# LoRasPI.net
KiCad netlist of a schematic drawn in EAGLE
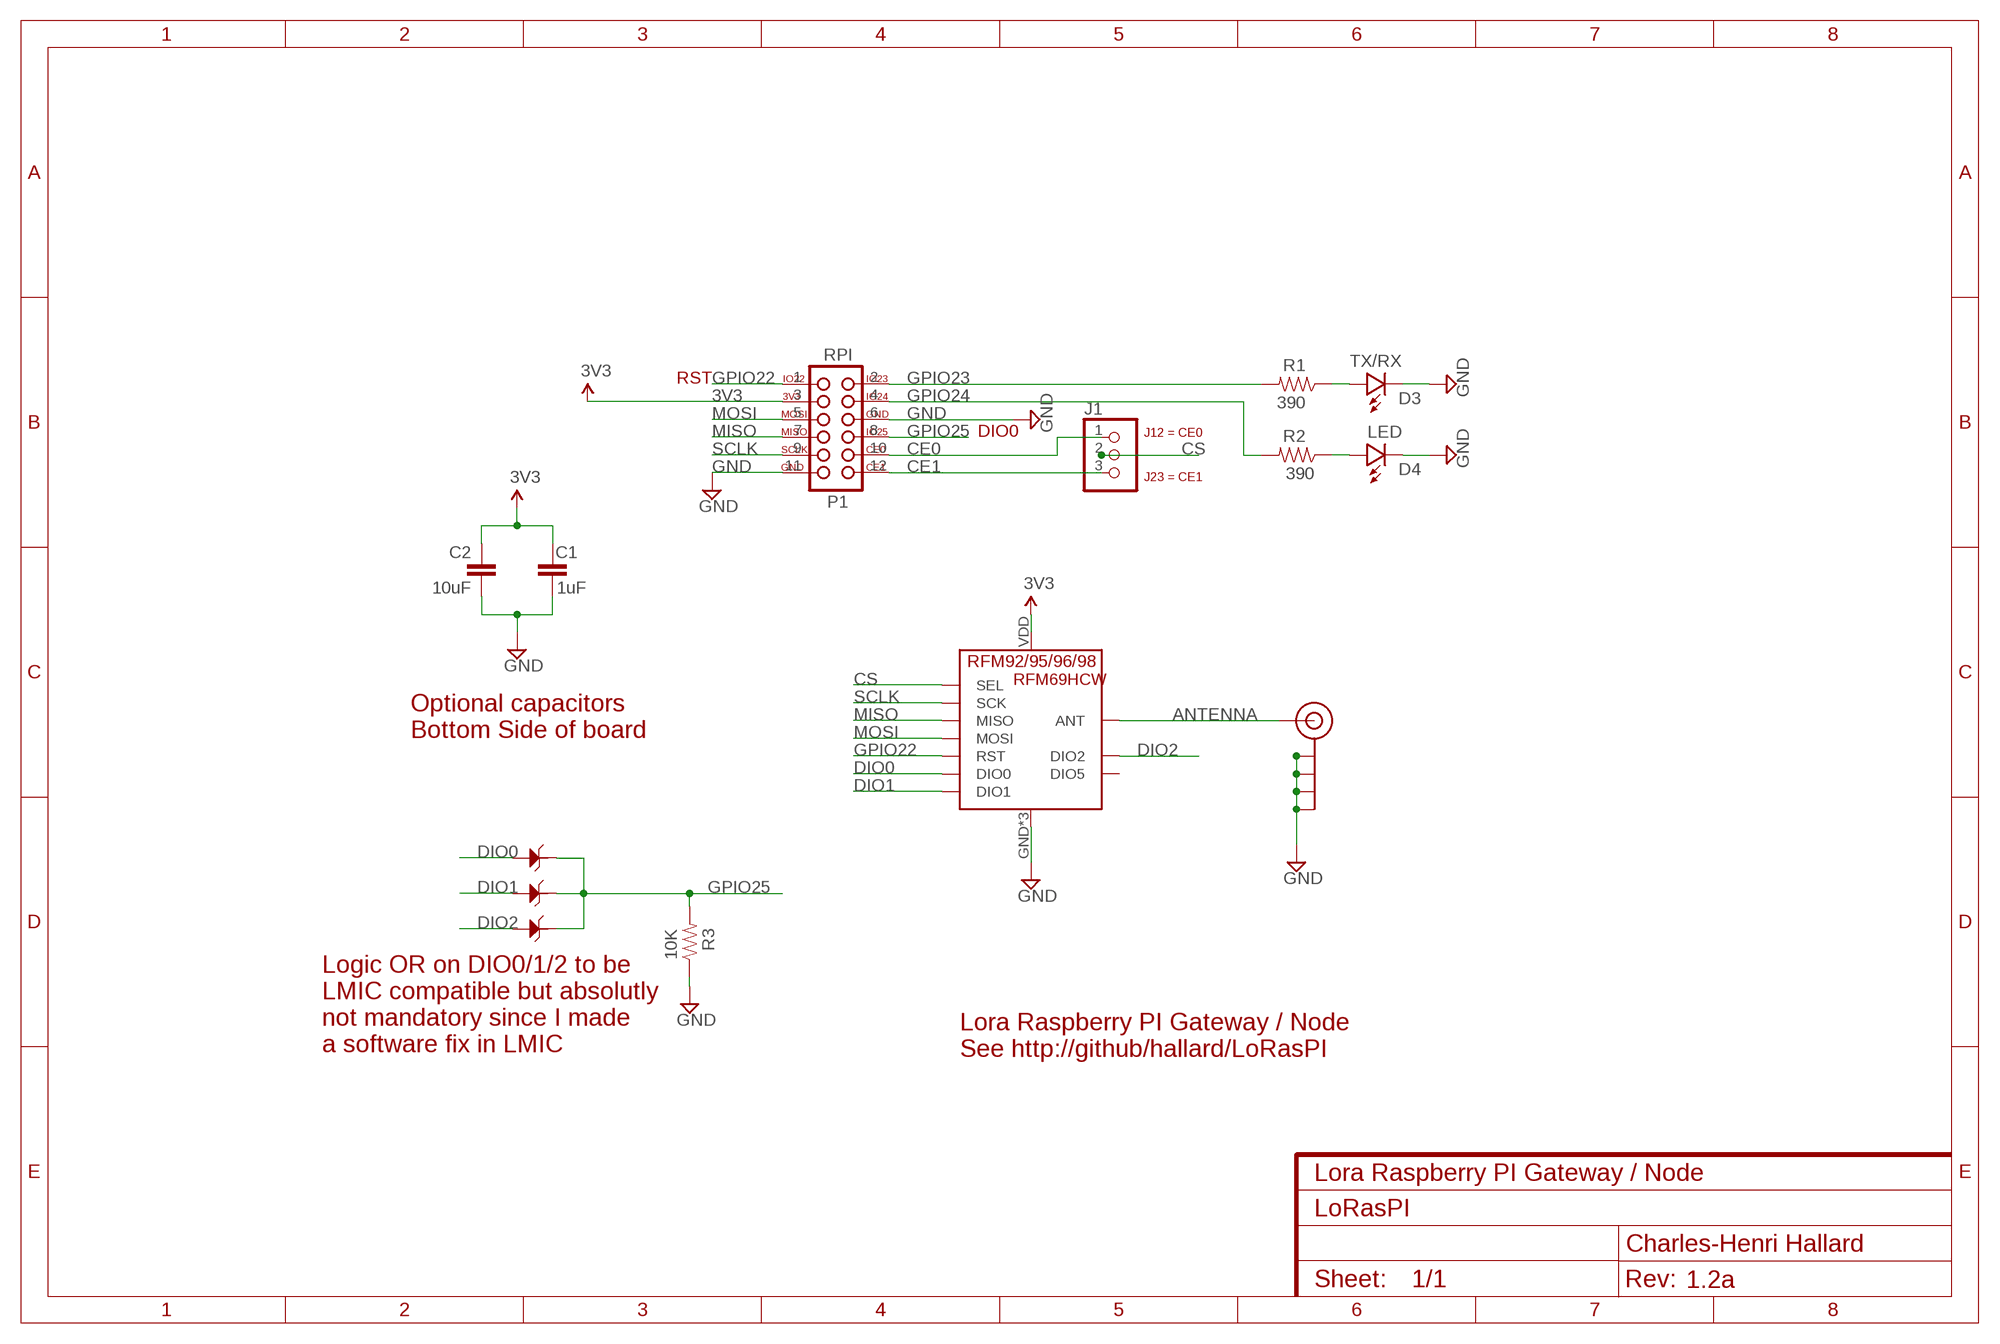
[diagram p0: schematic, sheet 1]

(export (version "E")
  (design (tool "Eeschema 10.0.6"))
  (components
    (comp (ref "C1")
      (value "1uF")
      (footprint "eagle-import:0805-CAP-LARGEPADS")
      (libsource (lib "eagle-import") (part "CAP0805-CAP-LARGEPADS"))
    )
    (comp (ref "C2")
      (value "10uF")
      (footprint "eagle-import:0805-CAP-LARGEPADS")
      (libsource (lib "eagle-import") (part "CAP0805-CAP-LARGEPADS"))
    )
    (comp (ref "D0")
      (value "1N4148")
      (footprint "eagle-import:SOD123-2.7X1.6")
      (libsource (lib "eagle-import") (part "D-ESD-2P-CESD5V0D1"))
    )
    (comp (ref "D1")
      (value "1N4148")
      (footprint "eagle-import:SOD123-2.7X1.6")
      (libsource (lib "eagle-import") (part "D-ESD-2P-CESD5V0D1"))
    )
    (comp (ref "D2")
      (value "1N4148")
      (footprint "eagle-import:SOD123-2.7X1.6")
      (libsource (lib "eagle-import") (part "D-ESD-2P-CESD5V0D1"))
    )
    (comp (ref "D3")
      (value "TX/RX")
      (footprint "eagle-import:0805-LED-LARGEPADS")
      (libsource (lib "eagle-import") (part "LED0805-LARGE"))
    )
    (comp (ref "D4")
      (value "LED")
      (footprint "eagle-import:0805-LED-LARGEPADS")
      (libsource (lib "eagle-import") (part "LED0805-LARGE"))
    )
    (comp (ref "HOPE-RF")
      (value "RFM92/95/96/98")
      (footprint "eagle-import:RFM95")
      (libsource (lib "eagle-import") (part "RFM95"))
    )
    (comp (ref "J$1")
      (value "ANTENNATINY")
      (footprint "eagle-import:SMA_UFL_PAD_TINY")
      (libsource (lib "eagle-import") (part "ANTENNATINY"))
    )
    (comp (ref "J1")
      (value "JUMPER_1X30805")
      (footprint "eagle-import:JP3_0805")
      (fields
        (field (name "J12") "optA")
        (field (name "J23") "optB")
        (field (name "J12_1") "CE0")
        (field (name "J23_1") "CE1")
      )
      (libsource (lib "eagle-import") (part "JUMPER_1X30805"))
    )
    (comp (ref "R1")
      (value "390")
      (footprint "eagle-import:0805-RES")
      (libsource (lib "eagle-import") (part "RESISTOR0805-RES"))
    )
    (comp (ref "R2")
      (value "390")
      (footprint "eagle-import:0805-RES")
      (libsource (lib "eagle-import") (part "RESISTOR0805-RES"))
    )
    (comp (ref "R3")
      (value "10K")
      (footprint "eagle-import:0805-RES")
      (libsource (lib "eagle-import") (part "RESISTOR0805-RES"))
    )
    (comp (ref "U$2")
      (value "RASPBERRY_PI_2X6_BOTTOM")
      (footprint "eagle-import:2X06_LOCK")
      (libsource (lib "eagle-import") (part "RASPBERRY_PI_2X6_BOTTOM"))
    )
  )
  (nets
    (net (code "1") (name "/ANTENNA") (class "Default")
      (node (ref "HOPE-RF") (pin "ANT") (pinfunction "ANT_ANT") (pintype "passive"))
      (node (ref "J$1") (pin "ANT1") (pinfunction "SIGNAL_ANT1") (pintype "bidirectional"))
      (node (ref "J$1") (pin "ANT2") (pinfunction "SIGNAL_ANT2") (pintype "bidirectional"))
      (node (ref "J$1") (pin "ANT3") (pinfunction "SIGNAL_ANT3") (pintype "bidirectional"))
    )
    (net (code "2") (name "/CE0") (class "Default")
      (node (ref "J1") (pin "1") (pinfunction "1_1") (pintype "passive"))
      (node (ref "U$2") (pin "10") (pinfunction "24_10") (pintype "bidirectional"))
    )
    (net (code "3") (name "/CE1") (class "Default")
      (node (ref "J1") (pin "3") (pinfunction "3_3") (pintype "passive"))
      (node (ref "U$2") (pin "12") (pinfunction "26_12") (pintype "bidirectional"))
    )
    (net (code "4") (name "/CS") (class "Default")
      (node (ref "HOPE-RF") (pin "NSS") (pinfunction "SEL_NSS") (pintype "input"))
      (node (ref "J1") (pin "2") (pinfunction "2_2") (pintype "passive"))
    )
    (net (code "5") (name "/DIO0") (class "Default")
      (node (ref "D0") (pin "1") (pinfunction "1_1") (pintype "bidirectional"))
      (node (ref "HOPE-RF") (pin "DIO0") (pinfunction "DIO0_DIO0") (pintype "open_collector"))
    )
    (net (code "6") (name "/DIO1") (class "Default")
      (node (ref "D1") (pin "1") (pinfunction "1_1") (pintype "bidirectional"))
      (node (ref "HOPE-RF") (pin "DIO1") (pinfunction "DIO1_DIO1") (pintype "open_collector"))
    )
    (net (code "7") (name "/DIO2") (class "Default")
      (node (ref "D2") (pin "1") (pinfunction "1_1") (pintype "bidirectional"))
      (node (ref "HOPE-RF") (pin "DIO2") (pinfunction "DIO2_DIO2") (pintype "open_collector"))
    )
    (net (code "8") (name "/GPIO22") (class "Default")
      (node (ref "HOPE-RF") (pin "RST") (pinfunction "RST_RST") (pintype "open_collector"))
      (node (ref "U$2") (pin "1") (pinfunction "15_1") (pintype "bidirectional"))
    )
    (net (code "9") (name "/GPIO23") (class "Default")
      (node (ref "R1") (pin "2") (pinfunction "2_2") (pintype "passive"))
      (node (ref "U$2") (pin "2") (pinfunction "16_2") (pintype "bidirectional"))
    )
    (net (code "10") (name "/GPIO24") (class "Default")
      (node (ref "R2") (pin "2") (pinfunction "2_2") (pintype "passive"))
      (node (ref "U$2") (pin "4") (pinfunction "18_4") (pintype "bidirectional"))
    )
    (net (code "11") (name "/GPIO25") (class "Default")
      (node (ref "D0") (pin "2") (pinfunction "2_2") (pintype "bidirectional"))
      (node (ref "D1") (pin "2") (pinfunction "2_2") (pintype "bidirectional"))
      (node (ref "D2") (pin "2") (pinfunction "2_2") (pintype "bidirectional"))
      (node (ref "R3") (pin "2") (pinfunction "2_2") (pintype "passive"))
      (node (ref "U$2") (pin "8") (pinfunction "22_8") (pintype "bidirectional"))
    )
    (net (code "12") (name "/MISO") (class "Default")
      (node (ref "HOPE-RF") (pin "MISO") (pinfunction "MISO_MISO") (pintype "input"))
      (node (ref "U$2") (pin "7") (pinfunction "21_7") (pintype "bidirectional"))
    )
    (net (code "13") (name "/MOSI") (class "Default")
      (node (ref "HOPE-RF") (pin "MOSI") (pinfunction "MOSI_MOSI") (pintype "output"))
      (node (ref "U$2") (pin "5") (pinfunction "19_5") (pintype "bidirectional"))
    )
    (net (code "14") (name "/SCLK") (class "Default")
      (node (ref "HOPE-RF") (pin "SCK") (pinfunction "SCK_SCK") (pintype "input"))
      (node (ref "U$2") (pin "9") (pinfunction "23_9") (pintype "bidirectional"))
    )
    (net (code "15") (name "3V3") (class "Default")
      (node (ref "C1") (pin "2") (pinfunction "2_2") (pintype "passive"))
      (node (ref "C2") (pin "2") (pinfunction "2_2") (pintype "passive"))
      (node (ref "HOPE-RF") (pin "VDD") (pinfunction "VCC_VDD") (pintype "power_in"))
      (node (ref "U$2") (pin "3") (pinfunction "17_3") (pintype "power_in"))
    )
    (net (code "16") (name "GND") (class "Default")
      (node (ref "C1") (pin "1") (pinfunction "1_1") (pintype "passive"))
      (node (ref "C2") (pin "1") (pinfunction "1_1") (pintype "passive"))
      (node (ref "D3") (pin "MINUS") (pinfunction "MINUS_MINUS") (pintype "passive"))
      (node (ref "D4") (pin "MINUS") (pinfunction "MINUS_MINUS") (pintype "passive"))
      (node (ref "HOPE-RF") (pin "GND") (pinfunction "GND_GND") (pintype "power_in"))
      (node (ref "HOPE-RF") (pin "GND1") (pinfunction "GND_GND1") (pintype "power_in"))
      (node (ref "HOPE-RF") (pin "GND2") (pinfunction "GND_GND2") (pintype "power_in"))
      (node (ref "J$1") (pin "GND1") (pinfunction "GND_GND1") (pintype "bidirectional"))
      (node (ref "J$1") (pin "GND2") (pinfunction "GND_GND2") (pintype "bidirectional"))
      (node (ref "J$1") (pin "GND3") (pinfunction "GND_GND3") (pintype "bidirectional"))
      (node (ref "J$1") (pin "GND4") (pinfunction "GND_GND4") (pintype "bidirectional"))
      (node (ref "R3") (pin "1") (pinfunction "1_1") (pintype "passive"))
      (node (ref "U$2") (pin "11") (pinfunction "25_11") (pintype "passive"))
      (node (ref "U$2") (pin "6") (pinfunction "20_6") (pintype "passive"))
    )
    (net (code "17") (name "Net-(D3-PadPLUS)") (class "Default")
      (node (ref "D3") (pin "PLUS") (pinfunction "PLUS_PLUS") (pintype "passive"))
      (node (ref "R1") (pin "1") (pinfunction "1_1") (pintype "passive"))
    )
    (net (code "18") (name "Net-(D4-PadPLUS)") (class "Default")
      (node (ref "D4") (pin "PLUS") (pinfunction "PLUS_PLUS") (pintype "passive"))
      (node (ref "R2") (pin "1") (pinfunction "1_1") (pintype "passive"))
    )
    (net (code "19") (name "unconnected-(HOPE-RF-PadDIO5)") (class "Default")
      (node (ref "HOPE-RF") (pin "DIO5") (pinfunction "DIO5_DIO5") (pintype "open_collector"))
    )
  )
)
